# rs485.net
KiCad netlist of a schematic drawn in Altium Designer
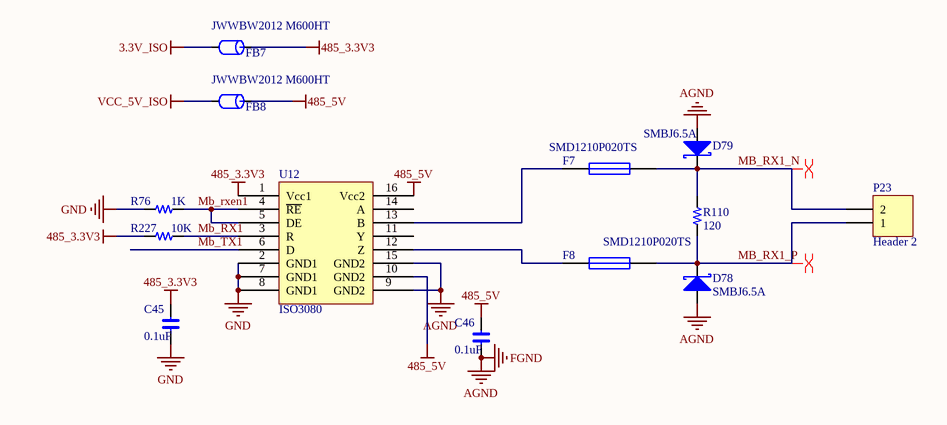
[diagram p0: rs485.SchDoc]

(export (version "E")
  (design (tool "Eeschema 10.0.6"))
  (components
    (comp (ref "C45")
      (value "0.1uF")
      (footprint "0603C")
      (description "C")
      (libsource (lib "Schlib_20110825") (part "C"))
    )
    (comp (ref "C46")
      (value "0.1uF")
      (footprint "0603C")
      (description "C")
      (libsource (lib "Schlib_20110825") (part "C"))
    )
    (comp (ref "D78")
      (value "SMBJ6.5A")
      (footprint "SMB")
      (description "Schottky Diode")
      (libsource (lib "*") (part "DIODE S"))
    )
    (comp (ref "D79")
      (value "SMBJ6.5A")
      (footprint "SMB")
      (description "Schottky Diode")
      (libsource (lib "*") (part "DIODE S"))
    )
    (comp (ref "F7")
      (value "SMD1210P020TS")
      (footprint "1206R")
      (description "Fuse")
      (fields (field (name "PUBLISHER") "Altium Limited"))
      (libsource (lib "Miscellaneous Devices") (part "Fuse 1"))
    )
    (comp (ref "F8")
      (value "SMD1210P020TS")
      (footprint "1206R")
      (description "Fuse")
      (fields (field (name "PUBLISHER") "Altium Limited"))
      (libsource (lib "Miscellaneous Devices") (part "Fuse 1"))
    )
    (comp (ref "FB7")
      (value "JWWBW2012 M600HT")
      (footprint "0805CZ")
      (libsource (lib "Schlib_20110825") (part "FB"))
    )
    (comp (ref "FB8")
      (value "JWWBW2012 M600HT")
      (footprint "0805CZ")
      (libsource (lib "Schlib_20110825") (part "FB"))
    )
    (comp (ref "P23")
      (value "Header 2")
      (footprint "2X2.54MMZ")
      (description "Header, 2-Pin")
      (fields (field (name "PUBLISHER") "Altium Limited"))
      (libsource (lib "Miscellaneous Connectors") (part "Header 2"))
    )
    (comp (ref "R76") (value "1K") (footprint "0603R") (description "R") (libsource (lib "JRJ_1") (part "R")))
    (comp (ref "R110")
      (value "120")
      (footprint "0603R")
      (description "R")
      (libsource (lib "JRJ_1") (part "R"))
    )
    (comp (ref "R227")
      (value "10K")
      (footprint "0603R")
      (description "R")
      (libsource (lib "JRJ_1") (part "R"))
    )
    (comp (ref "U12") (value "ISO3080") (footprint "SO-16") (libsource (lib "Schlib1") (part "ISO3080")))
  )
  (nets
    (net (code "1") (name "/MB_RX1_N") (class "Default")
      (node (ref "D79") (pin "2") (pinfunction "K_2") (pintype "passive"))
      (node (ref "F7") (pin "2") (pinfunction "2_2") (pintype "passive"))
      (node (ref "P23") (pin "2") (pinfunction "2_2") (pintype "passive"))
      (node (ref "R110") (pin "1") (pintype "passive"))
    )
    (net (code "2") (name "/MB_RX1_P") (class "Default")
      (node (ref "D78") (pin "2") (pinfunction "K_2") (pintype "passive"))
      (node (ref "F8") (pin "2") (pinfunction "2_2") (pintype "passive"))
      (node (ref "P23") (pin "1") (pinfunction "1_1") (pintype "passive"))
      (node (ref "R110") (pin "2") (pintype "passive"))
    )
    (net (code "3") (name "/Mb_RX1") (class "Default")
      (node (ref "R227") (pin "1") (pintype "passive"))
      (node (ref "U12") (pin "3") (pinfunction "R_3") (pintype "passive"))
    )
    (net (code "4") (name "/Mb_TX1") (class "Default")
      (node (ref "U12") (pin "6") (pinfunction "D_6") (pintype "passive"))
    )
    (net (code "5") (name "/Mb_rxen1") (class "Default")
      (node (ref "R76") (pin "1") (pintype "passive"))
      (node (ref "U12") (pin "4") (pinfunction "~{RE}_4") (pintype "passive"))
      (node (ref "U12") (pin "5") (pinfunction "DE_5") (pintype "passive"))
    )
    (net (code "6") (name "3.3V_ISO") (class "Default") (node (ref "FB7") (pin "2") (pintype "passive")))
    (net (code "7") (name "485_3.3V3") (class "Default")
      (node (ref "C45") (pin "2") (pintype "passive"))
      (node (ref "FB7") (pin "1") (pintype "passive"))
      (node (ref "R227") (pin "2") (pintype "passive"))
      (node (ref "U12") (pin "1") (pinfunction "Vcc1_1") (pintype "passive"))
    )
    (net (code "8") (name "485_5V") (class "Default")
      (node (ref "C46") (pin "2") (pintype "passive"))
      (node (ref "FB8") (pin "1") (pintype "passive"))
      (node (ref "U12") (pin "10") (pinfunction "GND2_10") (pintype "passive"))
      (node (ref "U12") (pin "16") (pinfunction "Vcc2_16") (pintype "passive"))
    )
    (net (code "9") (name "AGND") (class "Default")
      (node (ref "C46") (pin "1") (pintype "passive"))
      (node (ref "D78") (pin "1") (pinfunction "A_1") (pintype "passive"))
      (node (ref "D79") (pin "1") (pinfunction "A_1") (pintype "passive"))
      (node (ref "U12") (pin "15") (pinfunction "GND2_15") (pintype "passive"))
      (node (ref "U12") (pin "9") (pinfunction "GND2_9") (pintype "passive"))
    )
    (net (code "10") (name "GND") (class "Default")
      (node (ref "C45") (pin "1") (pintype "passive"))
      (node (ref "R76") (pin "2") (pintype "passive"))
      (node (ref "U12") (pin "2") (pinfunction "GND1_2") (pintype "passive"))
      (node (ref "U12") (pin "7") (pinfunction "GND1_7") (pintype "passive"))
      (node (ref "U12") (pin "8") (pinfunction "GND1_8") (pintype "passive"))
    )
    (net (code "11") (name "Net-(U12-B)") (class "Default")
      (node (ref "F7") (pin "1") (pinfunction "1_1") (pintype "passive"))
      (node (ref "U12") (pin "13") (pinfunction "B_13") (pintype "passive"))
    )
    (net (code "12") (name "Net-(U12-Z)") (class "Default")
      (node (ref "F8") (pin "1") (pinfunction "1_1") (pintype "passive"))
      (node (ref "U12") (pin "12") (pinfunction "Z_12") (pintype "passive"))
    )
    (net (code "13") (name "VCC_5V_ISO") (class "Default") (node (ref "FB8") (pin "2") (pintype "passive")))
    (net (code "14") (name "unconnected-(U12-A-Pad14)") (class "Default")
      (node (ref "U12") (pin "14") (pinfunction "A_14") (pintype "passive"))
    )
    (net (code "15") (name "unconnected-(U12-Y-Pad11)") (class "Default")
      (node (ref "U12") (pin "11") (pinfunction "Y_11") (pintype "passive"))
    )
  )
)
